# Arduino-Pro-Mini_ISP.net
KiCad netlist of a schematic drawn in EAGLE
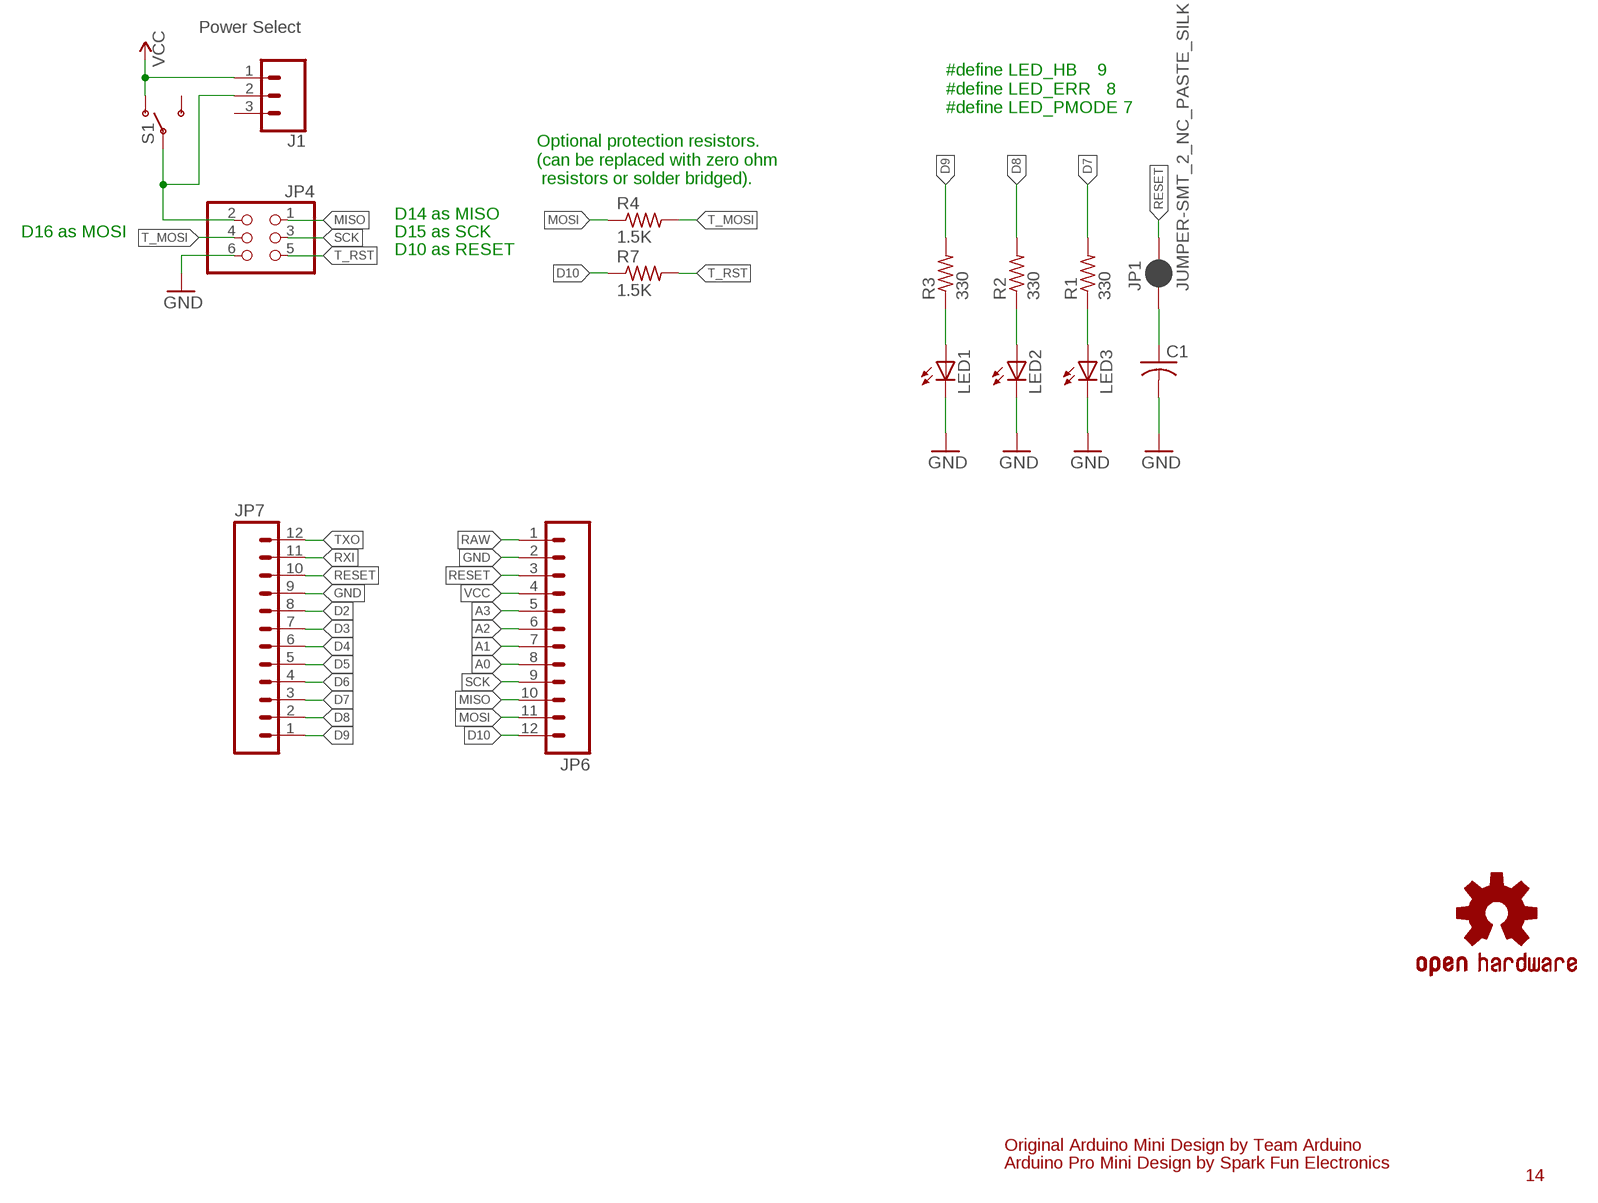
[diagram p0: schematic, sheet 1]

(export (version "E")
  (design (tool "Eeschema 10.0.6"))
  (components
    (comp (ref "C1")
      (value "C-USC0805")
      (footprint "eagle-import:C0805")
      (libsource (lib "eagle-import") (part "C-USC0805"))
    )
    (comp (ref "J1")
      (value "CONN_03")
      (footprint "eagle-import:1X03")
      (libsource (lib "eagle-import") (part "CONN_03"))
    )
    (comp (ref "JP1")
      (value "JUMPER-SMT_2_NC_PASTE_SILK")
      (footprint "eagle-import:SMT-JUMPER_2_NC_PASTE_SILK")
      (libsource (lib "eagle-import") (part "JUMPER-SMT_2_NC_PASTE_SILK"))
    )
    (comp (ref "JP4")
      (value "PINHD-2X3")
      (footprint "eagle-import:2X03")
      (libsource (lib "eagle-import") (part "PINHD-2X3"))
    )
    (comp (ref "JP6")
      (value "M12PTH")
      (footprint "eagle-import:1X12")
      (libsource (lib "eagle-import") (part "M12PTH"))
    )
    (comp (ref "JP7")
      (value "M12PTH")
      (footprint "eagle-import:1X12")
      (libsource (lib "eagle-import") (part "M12PTH"))
    )
    (comp (ref "LED1")
      (value "LEDCHIP-LED0805")
      (footprint "eagle-import:CHIP-LED0805")
      (libsource (lib "eagle-import") (part "LEDCHIP-LED0805"))
    )
    (comp (ref "LED2")
      (value "LEDCHIP-LED0805")
      (footprint "eagle-import:CHIP-LED0805")
      (libsource (lib "eagle-import") (part "LEDCHIP-LED0805"))
    )
    (comp (ref "LED3")
      (value "LEDCHIP-LED0805")
      (footprint "eagle-import:CHIP-LED0805")
      (libsource (lib "eagle-import") (part "LEDCHIP-LED0805"))
    )
    (comp (ref "R1")
      (value "330")
      (footprint "eagle-import:R0805")
      (libsource (lib "eagle-import") (part "R-US_R0805"))
    )
    (comp (ref "R2")
      (value "330")
      (footprint "eagle-import:R0805")
      (libsource (lib "eagle-import") (part "R-US_R0805"))
    )
    (comp (ref "R3")
      (value "330")
      (footprint "eagle-import:R0805")
      (libsource (lib "eagle-import") (part "R-US_R0805"))
    )
    (comp (ref "R4")
      (value "1.5K")
      (footprint "eagle-import:R0805")
      (libsource (lib "eagle-import") (part "R-US_R0805"))
    )
    (comp (ref "R7")
      (value "1.5K")
      (footprint "eagle-import:R0805")
      (libsource (lib "eagle-import") (part "R-US_R0805"))
    )
    (comp (ref "S1")
      (value "Power Select")
      (footprint "eagle-import:AYZ0202")
      (libsource (lib "eagle-import") (part "SWITCH-SPSTSMD"))
    )
    (comp (ref "U$3")
      (value "OSHW-LOGOS")
      (footprint "eagle-import:OSHW-LOGO-S")
      (libsource (lib "eagle-import") (part "OSHW-LOGOS"))
    )
  )
  (nets
    (net (code "1") (name "A0") (class "Default")
      (node (ref "JP6") (pin "8") (pinfunction "8_8") (pintype "passive"))
    )
    (net (code "2") (name "A1") (class "Default")
      (node (ref "JP6") (pin "7") (pinfunction "7_7") (pintype "passive"))
    )
    (net (code "3") (name "A2") (class "Default")
      (node (ref "JP6") (pin "6") (pinfunction "6_6") (pintype "passive"))
    )
    (net (code "4") (name "A3") (class "Default")
      (node (ref "JP6") (pin "5") (pinfunction "5_5") (pintype "passive"))
    )
    (net (code "5") (name "D2") (class "Default")
      (node (ref "JP7") (pin "8") (pinfunction "8_8") (pintype "passive"))
    )
    (net (code "6") (name "D3") (class "Default")
      (node (ref "JP7") (pin "7") (pinfunction "7_7") (pintype "passive"))
    )
    (net (code "7") (name "D4") (class "Default")
      (node (ref "JP7") (pin "6") (pinfunction "6_6") (pintype "passive"))
    )
    (net (code "8") (name "D5") (class "Default")
      (node (ref "JP7") (pin "5") (pinfunction "5_5") (pintype "passive"))
    )
    (net (code "9") (name "D6") (class "Default")
      (node (ref "JP7") (pin "4") (pinfunction "4_4") (pintype "passive"))
    )
    (net (code "10") (name "D7") (class "Default")
      (node (ref "JP7") (pin "3") (pinfunction "3_3") (pintype "passive"))
      (node (ref "R1") (pin "2") (pinfunction "2_2") (pintype "passive"))
    )
    (net (code "11") (name "D8") (class "Default")
      (node (ref "JP7") (pin "2") (pinfunction "2_2") (pintype "passive"))
      (node (ref "R2") (pin "2") (pinfunction "2_2") (pintype "passive"))
    )
    (net (code "12") (name "D9") (class "Default")
      (node (ref "JP7") (pin "1") (pinfunction "1_1") (pintype "passive"))
      (node (ref "R3") (pin "2") (pinfunction "2_2") (pintype "passive"))
    )
    (net (code "13") (name "D10") (class "Default")
      (node (ref "JP6") (pin "12") (pinfunction "12_12") (pintype "passive"))
      (node (ref "R7") (pin "1") (pinfunction "1_1") (pintype "passive"))
    )
    (net (code "14") (name "GND") (class "Default")
      (node (ref "C1") (pin "2") (pinfunction "2_2") (pintype "passive"))
      (node (ref "JP4") (pin "6") (pinfunction "6_6") (pintype "passive"))
      (node (ref "JP6") (pin "2") (pinfunction "2_2") (pintype "passive"))
      (node (ref "JP7") (pin "9") (pinfunction "9_9") (pintype "passive"))
      (node (ref "LED1") (pin "C") (pinfunction "C_C") (pintype "passive"))
      (node (ref "LED2") (pin "C") (pinfunction "C_C") (pintype "passive"))
      (node (ref "LED3") (pin "C") (pinfunction "C_C") (pintype "passive"))
    )
    (net (code "15") (name "MISO") (class "Default")
      (node (ref "JP4") (pin "1") (pinfunction "1_1") (pintype "passive"))
      (node (ref "JP6") (pin "10") (pinfunction "10_10") (pintype "passive"))
    )
    (net (code "16") (name "MOSI") (class "Default")
      (node (ref "JP6") (pin "11") (pinfunction "11_11") (pintype "passive"))
      (node (ref "R4") (pin "1") (pinfunction "1_1") (pintype "passive"))
    )
    (net (code "17") (name "Net-(C1-Pad1)") (class "Default")
      (node (ref "C1") (pin "1") (pinfunction "1_1") (pintype "passive"))
      (node (ref "JP1") (pin "1") (pinfunction "1_1") (pintype "passive"))
    )
    (net (code "18") (name "Net-(LED1-PadA)") (class "Default")
      (node (ref "LED1") (pin "A") (pinfunction "A_A") (pintype "passive"))
      (node (ref "R3") (pin "1") (pinfunction "1_1") (pintype "passive"))
    )
    (net (code "19") (name "Net-(LED2-PadA)") (class "Default")
      (node (ref "LED2") (pin "A") (pinfunction "A_A") (pintype "passive"))
      (node (ref "R2") (pin "1") (pinfunction "1_1") (pintype "passive"))
    )
    (net (code "20") (name "Net-(LED3-PadA)") (class "Default")
      (node (ref "LED3") (pin "A") (pinfunction "A_A") (pintype "passive"))
      (node (ref "R1") (pin "1") (pinfunction "1_1") (pintype "passive"))
    )
    (net (code "21") (name "Net-(S1-P)") (class "Default")
      (node (ref "J1") (pin "2") (pinfunction "2_2") (pintype "passive"))
      (node (ref "JP4") (pin "2") (pinfunction "2_2") (pintype "passive"))
      (node (ref "S1") (pin "2") (pinfunction "P_2") (pintype "passive"))
    )
    (net (code "22") (name "RAW") (class "Default")
      (node (ref "JP6") (pin "1") (pinfunction "1_1") (pintype "passive"))
    )
    (net (code "23") (name "RESET") (class "Default")
      (node (ref "JP1") (pin "2") (pinfunction "2_2") (pintype "passive"))
      (node (ref "JP6") (pin "3") (pinfunction "3_3") (pintype "passive"))
      (node (ref "JP7") (pin "10") (pinfunction "10_10") (pintype "passive"))
    )
    (net (code "24") (name "RXI") (class "Default")
      (node (ref "JP7") (pin "11") (pinfunction "11_11") (pintype "passive"))
    )
    (net (code "25") (name "SCK") (class "Default")
      (node (ref "JP4") (pin "3") (pinfunction "3_3") (pintype "passive"))
      (node (ref "JP6") (pin "9") (pinfunction "9_9") (pintype "passive"))
    )
    (net (code "26") (name "TXO") (class "Default")
      (node (ref "JP7") (pin "12") (pinfunction "12_12") (pintype "passive"))
    )
    (net (code "27") (name "T_MOSI") (class "Default")
      (node (ref "JP4") (pin "4") (pinfunction "4_4") (pintype "passive"))
      (node (ref "R4") (pin "2") (pinfunction "2_2") (pintype "passive"))
    )
    (net (code "28") (name "T_RST") (class "Default")
      (node (ref "JP4") (pin "5") (pinfunction "5_5") (pintype "passive"))
      (node (ref "R7") (pin "2") (pinfunction "2_2") (pintype "passive"))
    )
    (net (code "29") (name "VCC") (class "Default")
      (node (ref "J1") (pin "1") (pinfunction "1_1") (pintype "passive"))
      (node (ref "JP6") (pin "4") (pinfunction "4_4") (pintype "passive"))
      (node (ref "S1") (pin "1") (pinfunction "O_1") (pintype "passive"))
    )
    (net (code "30") (name "unconnected-(J1-Pad3)") (class "Default")
      (node (ref "J1") (pin "3") (pinfunction "3_3") (pintype "passive"))
    )
    (net (code "31") (name "unconnected-(S1-S-Pad3)") (class "Default")
      (node (ref "S1") (pin "3") (pinfunction "S_3") (pintype "passive"))
    )
  )
)
